# R3S601.net
KiCad netlist of a schematic drawn in Altium Designer
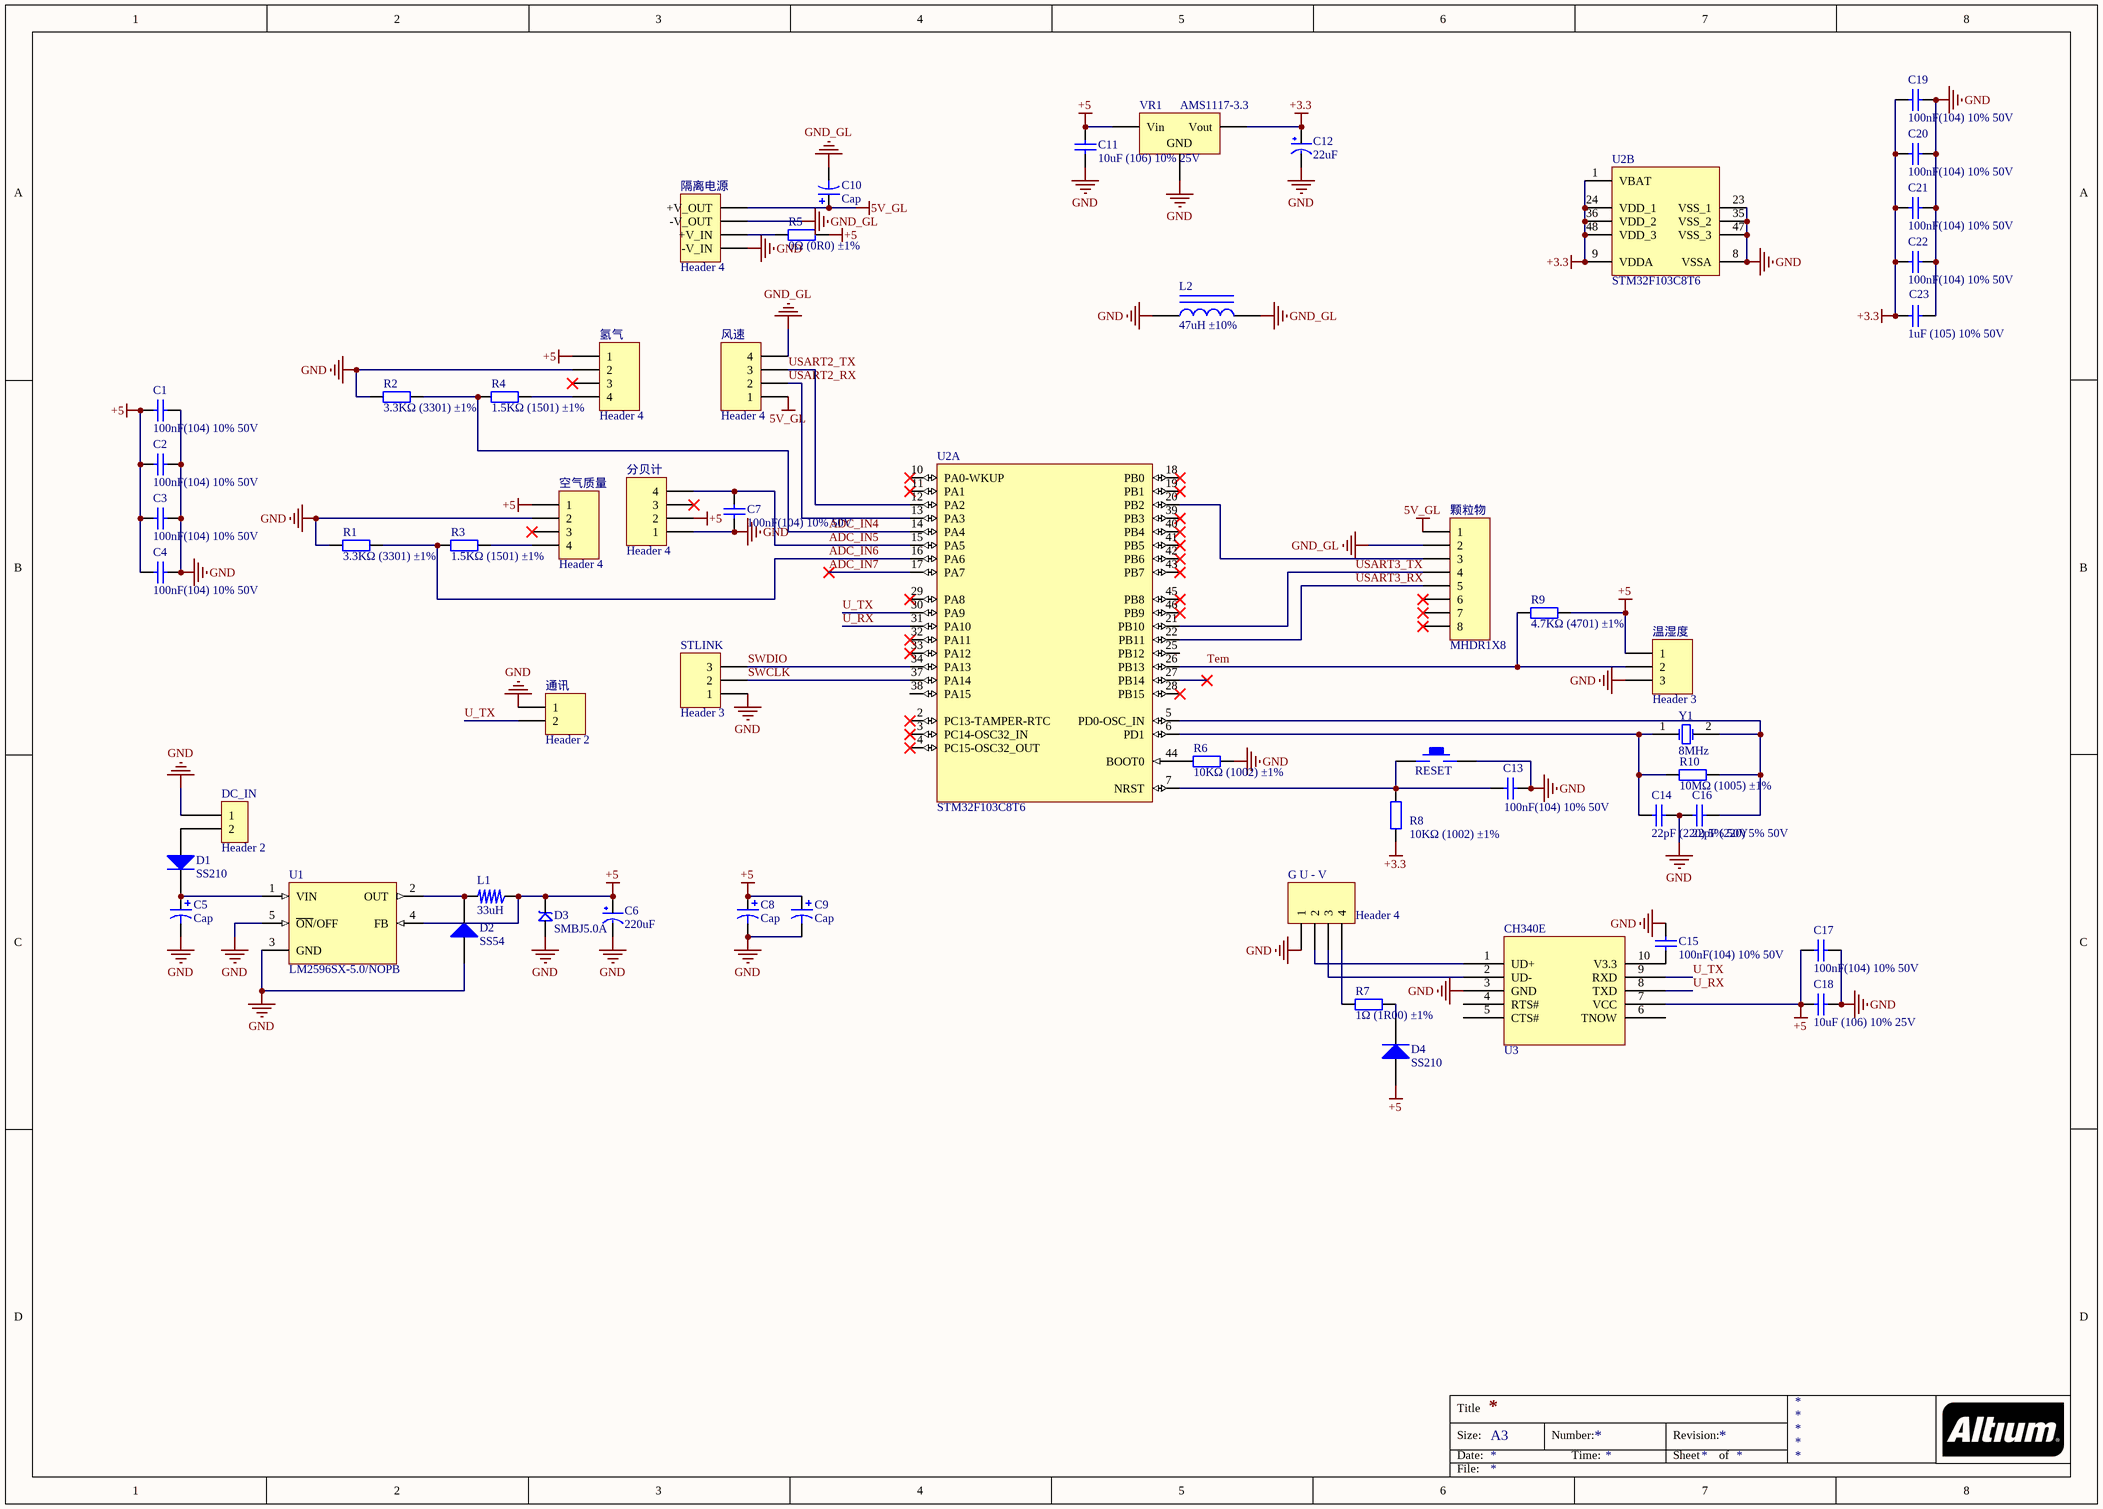
[diagram p0: R3S601.SchDoc]

(export (version "E")
  (design (tool "Eeschema 10.0.6"))
  (components
    (comp (ref "C1")
      (value "100nF(104) 10% 50V")
      (footprint "LC-0805_C")
      (description "贴片电容")
      (libsource (lib "Miscellaneous Devices LC") (part "0805 100nF(104) 10% 50V"))
    )
    (comp (ref "C2")
      (value "100nF(104) 10% 50V")
      (footprint "LC-0805_C")
      (description "贴片电容")
      (libsource (lib "Miscellaneous Devices LC") (part "0805 100nF(104) 10% 50V"))
    )
    (comp (ref "C3")
      (value "100nF(104) 10% 50V")
      (footprint "LC-0805_C")
      (description "贴片电容")
      (libsource (lib "Miscellaneous Devices LC") (part "0805 100nF(104) 10% 50V"))
    )
    (comp (ref "C4")
      (value "100nF(104) 10% 50V")
      (footprint "LC-0805_C")
      (description "贴片电容")
      (libsource (lib "Miscellaneous Devices LC") (part "0805 100nF(104) 10% 50V"))
    )
    (comp (ref "C5")
      (value "Cap")
      (footprint "CAP-DIP-3.5")
      (description "Cap_DIP")
      (libsource (lib "AD_Chip_Y") (part "Cap_DIP"))
    )
    (comp (ref "C6")
      (value "220uF")
      (footprint "CC6.56.5")
      (libsource (lib "Explorer STM32F407封装库") (part "CAP"))
    )
    (comp (ref "C7")
      (value "100nF(104) 10% 50V")
      (footprint "LC-0805_C")
      (description "贴片电容")
      (libsource (lib "Miscellaneous Devices LC") (part "0805 100nF(104) 10% 50V"))
    )
    (comp (ref "C8")
      (value "Cap")
      (footprint "CAP-DIP-3.5")
      (description "Cap_DIP")
      (libsource (lib "AD_Chip_Y") (part "Cap_DIP"))
    )
    (comp (ref "C9")
      (value "Cap")
      (footprint "CAP-DIP-5.0")
      (description "Cap_DIP")
      (libsource (lib "AD_Chip_Y") (part "Cap_DIP"))
    )
    (comp (ref "C10")
      (value "Cap")
      (footprint "CAP-DIP-3.5")
      (description "Cap_DIP")
      (libsource (lib "AD_Chip_Y") (part "Cap_DIP"))
    )
    (comp (ref "C11")
      (value "10uF (106) 10% 25V")
      (footprint "LC-0805_C")
      (description "贴片电容")
      (libsource (lib "Miscellaneous Devices LC") (part "0805 10uF (106) 10% 25V"))
    )
    (comp (ref "C12")
      (value "22uF")
      (footprint "CC6.56.5")
      (libsource (lib "Explorer STM32F407封装库") (part "CAP"))
    )
    (comp (ref "C13")
      (value "100nF(104) 10% 50V")
      (footprint "LC-0805_C")
      (description "贴片电容")
      (libsource (lib "Miscellaneous Devices LC") (part "0805 100nF(104) 10% 50V"))
    )
    (comp (ref "C14")
      (value "22pF (220) 5% 50V")
      (footprint "LC-0805_C")
      (description "贴片电容")
      (libsource (lib "Miscellaneous Devices LC") (part "0805 22pF (220) 5% 50V"))
    )
    (comp (ref "C15")
      (value "100nF(104) 10% 50V")
      (footprint "LC-0805_C")
      (description "贴片电容")
      (libsource (lib "Miscellaneous Devices LC") (part "0805 100nF(104) 10% 50V"))
    )
    (comp (ref "C16")
      (value "22pF (220) 5% 50V")
      (footprint "LC-0805_C")
      (description "贴片电容")
      (libsource (lib "Miscellaneous Devices LC") (part "0805 22pF (220) 5% 50V"))
    )
    (comp (ref "C17")
      (value "100nF(104) 10% 50V")
      (footprint "LC-0805_C")
      (description "贴片电容")
      (libsource (lib "Miscellaneous Devices LC") (part "0805 100nF(104) 10% 50V"))
    )
    (comp (ref "C18")
      (value "10uF (106) 10% 25V")
      (footprint "LC-0805_C")
      (description "贴片电容")
      (libsource (lib "Miscellaneous Devices LC") (part "0805 10uF (106) 10% 25V"))
    )
    (comp (ref "C19")
      (value "100nF(104) 10% 50V")
      (footprint "LC-0805_C")
      (description "贴片电容")
      (libsource (lib "Miscellaneous Devices LC") (part "0805 100nF(104) 10% 50V"))
    )
    (comp (ref "C20")
      (value "100nF(104) 10% 50V")
      (footprint "LC-0805_C")
      (description "贴片电容")
      (libsource (lib "Miscellaneous Devices LC") (part "0805 100nF(104) 10% 50V"))
    )
    (comp (ref "C21")
      (value "100nF(104) 10% 50V")
      (footprint "LC-0805_C")
      (description "贴片电容")
      (libsource (lib "Miscellaneous Devices LC") (part "0805 100nF(104) 10% 50V"))
    )
    (comp (ref "C22")
      (value "100nF(104) 10% 50V")
      (footprint "LC-0805_C")
      (description "贴片电容")
      (libsource (lib "Miscellaneous Devices LC") (part "0805 100nF(104) 10% 50V"))
    )
    (comp (ref "C23")
      (value "1uF (105) 10% 50V")
      (footprint "LC-0805_C")
      (description "贴片电容")
      (libsource (lib "Miscellaneous Devices LC") (part "0805 1uF (105) 10% 50V"))
    )
    (comp (ref "D1")
      (value "SS210")
      (footprint "LC-SMA(DO-214AC)_S1")
      (description "二极管")
      (libsource (lib "Miscellaneous Devices LC") (part "SMA(DO-214AC) SS210"))
    )
    (comp (ref "D2")
      (value "SS54")
      (footprint "LC-SMA(DO-214AC)_S1")
      (description "二极管")
      (libsource (lib "Miscellaneous Devices LC") (part "SMA(DO-214AC) SS54"))
    )
    (comp (ref "D3")
      (value "SMBJ5.0A")
      (footprint "SMBJ")
      (description "TVS")
      (libsource (lib "Explorer STM32F407封装库") (part "SMBJ"))
    )
    (comp (ref "D4")
      (value "SS210")
      (footprint "LC-SMA(DO-214AC)_S1")
      (description "二极管")
      (libsource (lib "Miscellaneous Devices LC") (part "SMA(DO-214AC) SS210"))
    )
    (comp (ref "DC_IN")
      (value "Header 2")
      (footprint "VH-2A - Circle Hole")
      (description "贴片2p座")
      (libsource (lib "AD_Chip_Y") (part "Header 2"))
    )
    (comp (ref "G U - V")
      (value "Header 4")
      (footprint "HDR1X4")
      (description "Header, 4-Pin")
      (fields (field (name "PUBLISHER") "Altium Limited"))
      (libsource (lib "Miscellaneous Connectors") (part "Header 4"))
    )
    (comp (ref "L1")
      (value "33uH")
      (footprint "L_SOP74")
      (libsource (lib "Explorer STM32F407封装库") (part "L_SOP"))
    )
    (comp (ref "L2")
      (value "47uH ±10%")
      (footprint "LC-0805_L")
      (description "贴片电感")
      (libsource (lib "Miscellaneous Devices LC") (part "0805 47uH 10%"))
    )
    (comp (ref "R1")
      (value "3.3KΩ (3301) ±1%")
      (footprint "LC-0805_R")
      (description "贴片电阻")
      (libsource (lib "Miscellaneous Devices LC") (part "0805 3.3KΩ (3301) 1%"))
    )
    (comp (ref "R2")
      (value "3.3KΩ (3301) ±1%")
      (footprint "LC-0805_R")
      (description "贴片电阻")
      (libsource (lib "Miscellaneous Devices LC") (part "0805 3.3KΩ (3301) 1%"))
    )
    (comp (ref "R3")
      (value "1.5KΩ (1501) ±1%")
      (footprint "LC-0805_R")
      (description "贴片电阻")
      (libsource (lib "Miscellaneous Devices LC") (part "0805 1.5KΩ (1501) 1%"))
    )
    (comp (ref "R4")
      (value "1.5KΩ (1501) ±1%")
      (footprint "LC-0805_R")
      (description "贴片电阻")
      (libsource (lib "Miscellaneous Devices LC") (part "0805 1.5KΩ (1501) 1%"))
    )
    (comp (ref "R5")
      (value "0Ω (0R0) ±1%")
      (footprint "LC-0603_R")
      (description "贴片电阻")
      (libsource (lib "Miscellaneous Devices LC") (part "0603 0Ω (0R0) 1%"))
    )
    (comp (ref "R6")
      (value "10KΩ (1002) ±1%")
      (footprint "LC-0805_R")
      (description "贴片电阻")
      (libsource (lib "") (part "0805 10KΩ (1002) 1%_1"))
    )
    (comp (ref "R7")
      (value "1Ω (1R00) ±1%")
      (footprint "LC-0603_R")
      (description "贴片电阻")
      (libsource (lib "Miscellaneous Devices LC") (part "0603 1Ω (1R00) 1%"))
    )
    (comp (ref "R8")
      (value "10KΩ (1002) ±1%")
      (footprint "LC-0805_R")
      (description "贴片电阻")
      (libsource (lib "Miscellaneous Devices LC") (part "0805 10KΩ (1002) 1%"))
    )
    (comp (ref "R9")
      (value "4.7KΩ (4701) ±1%")
      (footprint "LC-0805_R")
      (description "贴片电阻")
      (libsource (lib "Miscellaneous Devices LC") (part "0805 4.7KΩ (4701) 1%"))
    )
    (comp (ref "R10")
      (value "10MΩ (1005) ±1%")
      (footprint "LC-0805_R")
      (description "贴片电阻")
      (libsource (lib "Miscellaneous Devices LC") (part "0805 10MΩ (1005) 1%"))
    )
    (comp (ref "RESET")
      (value "KEY_M")
      (footprint "KEY_M")
      (libsource (lib "Explorer STM32F407封装库") (part "KEY_M"))
    )
    (comp (ref "STLINK")
      (value "Header 3")
      (footprint "HDR1X3")
      (description "Header, 3-Pin")
      (fields (field (name "PUBLISHER") "Altium Limited"))
      (libsource (lib "Miscellaneous Connectors") (part "Header 3"))
    )
    (comp (ref "U1")
      (value "LM2596SX-5.0/NOPB")
      (footprint "LC-TO-263-5")
      (description "DC-DC芯片")
      (libsource (lib "Miscellaneous Devices LC") (part "LM2596SX-5.0/NOPB"))
    )
    (comp (ref "U2")
      (value "STM32F103C8T6")
      (footprint "LC-LQFP-48_7x7x05P")
      (description "ARM")
      (libsource (lib "Miscellaneous Devices LC") (part "STM32F103C8T6"))
    )
    (comp (ref "U3")
      (value "CH340E")
      (footprint "LC-MSOP-10")
      (description "USB")
      (libsource (lib "AD_Chip_Y") (part "CH340E"))
    )
    (comp (ref "VR1")
      (value "AMS1117-3.3")
      (footprint "LC-SOT-223")
      (description "低压差线性稳压(LDO)")
      (libsource (lib "Miscellaneous Devices LC") (part "SOT-223 AMS1117-3.3"))
    )
    (comp (ref "Y1")
      (value "8MHz")
      (footprint "XTAL_US")
      (description "Crystal Oscillator")
      (fields (field (name "PUBLISHER") "Altium Limited"))
      (libsource (lib "Explorer STM32F407封装库") (part "XTAL"))
    )
    (comp (ref "分贝计")
      (value "Header 4")
      (footprint "HDR1X4")
      (description "Header, 4-Pin")
      (fields (field (name "PUBLISHER") "Altium Limited"))
      (libsource (lib "") (part "Header 4_1"))
    )
    (comp (ref "氢气")
      (value "Header 4")
      (footprint "HDR1X4")
      (description "Header, 4-Pin")
      (fields (field (name "PUBLISHER") "Altium Limited"))
      (libsource (lib "") (part "Header 4_2"))
    )
    (comp (ref "温湿度")
      (value "Header 3")
      (footprint "HDR1X3")
      (description "Header, 3-Pin")
      (fields (field (name "PUBLISHER") "Altium Limited"))
      (libsource (lib "") (part "Header 3_1"))
    )
    (comp (ref "空气质量")
      (value "Header 4")
      (footprint "HDR1X4")
      (description "Header, 4-Pin")
      (fields (field (name "PUBLISHER") "Altium Limited"))
      (libsource (lib "") (part "Header 4_2"))
    )
    (comp (ref "通讯")
      (value "Header 2")
      (footprint "HDR1X2")
      (description "Header, 2-Pin")
      (fields (field (name "PUBLISHER") "Altium Limited"))
      (libsource (lib "Miscellaneous Connectors") (part "Header 2"))
    )
    (comp (ref "隔离电源")
      (value "Header 4")
      (footprint "HDR1X4")
      (description "Header, 4-Pin")
      (fields (field (name "PUBLISHER") "Altium Limited"))
      (libsource (lib "") (part "Header 4_3"))
    )
    (comp (ref "颗粒物")
      (value "MHDR1X8")
      (footprint "MHDR1X8")
      (description "Header, 8-Pin")
      (fields (field (name "PUBLISHER") "Altium Limited"))
      (libsource (lib "Miscellaneous Connectors") (part "MHDR1X8"))
    )
    (comp (ref "风速")
      (value "Header 4")
      (footprint "HDR1X4")
      (description "Header, 4-Pin")
      (fields (field (name "PUBLISHER") "Altium Limited"))
      (libsource (lib "") (part "Header 4_1"))
    )
  )
  (nets
    (net (code "1") (name "+3.3") (class "Default")
      (node (ref "C12") (pin "1") (pinfunction "VCC_1") (pintype "passive"))
      (node (ref "C19") (pin "2") (pinfunction "2_2") (pintype "passive"))
      (node (ref "C20") (pin "2") (pinfunction "2_2") (pintype "passive"))
      (node (ref "C21") (pin "2") (pinfunction "2_2") (pintype "passive"))
      (node (ref "C22") (pin "2") (pinfunction "2_2") (pintype "passive"))
      (node (ref "C23") (pin "2") (pinfunction "2_2") (pintype "passive"))
      (node (ref "R8") (pin "1") (pinfunction "1_1") (pintype "passive"))
      (node (ref "U2") (pin "1") (pinfunction "VBAT_1") (pintype "power_in"))
      (node (ref "U2") (pin "24") (pinfunction "VDD_1_24") (pintype "power_in"))
      (node (ref "U2") (pin "36") (pinfunction "VDD_2_36") (pintype "power_in"))
      (node (ref "U2") (pin "48") (pinfunction "VDD_3_48") (pintype "power_in"))
      (node (ref "U2") (pin "9") (pinfunction "VDDA_9") (pintype "power_in"))
      (node (ref "VR1") (pin "2") (pinfunction "Vout_2") (pintype "passive"))
    )
    (net (code "2") (name "+5") (class "Default")
      (node (ref "C1") (pin "1") (pinfunction "1_1") (pintype "passive"))
      (node (ref "C11") (pin "2") (pinfunction "2_2") (pintype "passive"))
      (node (ref "C17") (pin "1") (pinfunction "1_1") (pintype "passive"))
      (node (ref "C18") (pin "1") (pinfunction "1_1") (pintype "passive"))
      (node (ref "C2") (pin "1") (pinfunction "1_1") (pintype "passive"))
      (node (ref "C3") (pin "1") (pinfunction "1_1") (pintype "passive"))
      (node (ref "C4") (pin "1") (pinfunction "1_1") (pintype "passive"))
      (node (ref "C6") (pin "1") (pinfunction "VCC_1") (pintype "passive"))
      (node (ref "C8") (pin "1") (pinfunction "1_1") (pintype "passive"))
      (node (ref "C9") (pin "1") (pinfunction "1_1") (pintype "passive"))
      (node (ref "D3") (pin "2") (pintype "passive"))
      (node (ref "D4") (pin "1") (pinfunction "A_1") (pintype "passive"))
      (node (ref "L1") (pin "1") (pinfunction "1_1") (pintype "passive"))
      (node (ref "R5") (pin "2") (pinfunction "2_2") (pintype "passive"))
      (node (ref "R9") (pin "2") (pinfunction "2_2") (pintype "passive"))
      (node (ref "U1") (pin "4") (pinfunction "FB_4") (pintype "input"))
      (node (ref "U3") (pin "7") (pinfunction "VCC_7") (pintype "passive"))
      (node (ref "VR1") (pin "3") (pinfunction "Vin_3") (pintype "passive"))
      (node (ref "分贝计") (pin "2") (pinfunction "2_2") (pintype "passive"))
      (node (ref "氢气") (pin "1") (pinfunction "1_1") (pintype "passive"))
      (node (ref "温湿度") (pin "1") (pinfunction "1_1") (pintype "passive"))
      (node (ref "空气质量") (pin "1") (pinfunction "1_1") (pintype "passive"))
    )
    (net (code "3") (name "/ADC_IN4") (class "Default")
      (node (ref "R2") (pin "2") (pinfunction "2_2") (pintype "passive"))
      (node (ref "R4") (pin "1") (pinfunction "1_1") (pintype "passive"))
      (node (ref "U2") (pin "14") (pinfunction "PA4_14") (pintype "bidirectional"))
    )
    (net (code "4") (name "/ADC_IN5") (class "Default")
      (node (ref "C7") (pin "2") (pinfunction "2_2") (pintype "passive"))
      (node (ref "U2") (pin "15") (pinfunction "PA5_15") (pintype "bidirectional"))
      (node (ref "分贝计") (pin "4") (pinfunction "4_4") (pintype "passive"))
    )
    (net (code "5") (name "/ADC_IN6") (class "Default")
      (node (ref "R1") (pin "2") (pinfunction "2_2") (pintype "passive"))
      (node (ref "R3") (pin "1") (pinfunction "1_1") (pintype "passive"))
      (node (ref "U2") (pin "16") (pinfunction "PA6_16") (pintype "bidirectional"))
    )
    (net (code "6") (name "/ADC_IN7") (class "Default")
      (node (ref "U2") (pin "17") (pinfunction "PA7_17") (pintype "bidirectional+no_connect"))
    )
    (net (code "7") (name "/SWCLK") (class "Default")
      (node (ref "STLINK") (pin "2") (pinfunction "2_2") (pintype "passive"))
      (node (ref "U2") (pin "37") (pinfunction "PA14_37") (pintype "bidirectional"))
    )
    (net (code "8") (name "/SWDIO") (class "Default")
      (node (ref "STLINK") (pin "3") (pinfunction "3_3") (pintype "passive"))
      (node (ref "U2") (pin "34") (pinfunction "PA13_34") (pintype "bidirectional"))
    )
    (net (code "9") (name "/Tem") (class "Default")
      (node (ref "R9") (pin "1") (pinfunction "1_1") (pintype "passive"))
      (node (ref "U2") (pin "26") (pinfunction "PB13_26") (pintype "bidirectional"))
      (node (ref "温湿度") (pin "2") (pinfunction "2_2") (pintype "passive"))
    )
    (net (code "10") (name "/USART2_RX") (class "Default")
      (node (ref "U2") (pin "13") (pinfunction "PA3_13") (pintype "bidirectional"))
      (node (ref "风速") (pin "2") (pinfunction "2_2") (pintype "passive"))
    )
    (net (code "11") (name "/USART2_TX") (class "Default")
      (node (ref "U2") (pin "12") (pinfunction "PA2_12") (pintype "bidirectional"))
      (node (ref "风速") (pin "3") (pinfunction "3_3") (pintype "passive"))
    )
    (net (code "12") (name "/USART3_RX") (class "Default")
      (node (ref "U2") (pin "22") (pinfunction "PB11_22") (pintype "bidirectional"))
      (node (ref "颗粒物") (pin "5") (pinfunction "5_5") (pintype "passive"))
    )
    (net (code "13") (name "/USART3_TX") (class "Default")
      (node (ref "U2") (pin "21") (pinfunction "PB10_21") (pintype "bidirectional"))
      (node (ref "颗粒物") (pin "4") (pinfunction "4_4") (pintype "passive"))
    )
    (net (code "14") (name "/U_RX") (class "Default")
      (node (ref "U2") (pin "31") (pinfunction "PA10_31") (pintype "bidirectional"))
      (node (ref "U3") (pin "8") (pinfunction "TXD_8") (pintype "passive"))
    )
    (net (code "15") (name "/U_TX") (class "Default")
      (node (ref "U2") (pin "30") (pinfunction "PA9_30") (pintype "bidirectional"))
      (node (ref "U3") (pin "9") (pinfunction "RXD_9") (pintype "passive"))
      (node (ref "通讯") (pin "2") (pinfunction "2_2") (pintype "passive"))
    )
    (net (code "16") (name "5V_GL") (class "Default")
      (node (ref "C10") (pin "1") (pinfunction "1_1") (pintype "passive"))
      (node (ref "隔离电源") (pin "4") (pinfunction "+V_OUT_4") (pintype "passive"))
      (node (ref "颗粒物") (pin "1") (pinfunction "1_1") (pintype "passive"))
      (node (ref "风速") (pin "1") (pinfunction "1_1") (pintype "passive"))
    )
    (net (code "17") (name "GND") (class "Default")
      (node (ref "C1") (pin "2") (pinfunction "2_2") (pintype "passive"))
      (node (ref "C11") (pin "1") (pinfunction "1_1") (pintype "passive"))
      (node (ref "C12") (pin "2") (pinfunction "GND_2") (pintype "passive"))
      (node (ref "C13") (pin "1") (pinfunction "1_1") (pintype "passive"))
      (node (ref "C14") (pin "2") (pinfunction "2_2") (pintype "passive"))
      (node (ref "C15") (pin "2") (pinfunction "2_2") (pintype "passive"))
      (node (ref "C16") (pin "1") (pinfunction "1_1") (pintype "passive"))
      (node (ref "C17") (pin "2") (pinfunction "2_2") (pintype "passive"))
      (node (ref "C18") (pin "2") (pinfunction "2_2") (pintype "passive"))
      (node (ref "C19") (pin "1") (pinfunction "1_1") (pintype "passive"))
      (node (ref "C2") (pin "2") (pinfunction "2_2") (pintype "passive"))
      (node (ref "C20") (pin "1") (pinfunction "1_1") (pintype "passive"))
      (node (ref "C21") (pin "1") (pinfunction "1_1") (pintype "passive"))
      (node (ref "C22") (pin "1") (pinfunction "1_1") (pintype "passive"))
      (node (ref "C23") (pin "1") (pinfunction "1_1") (pintype "passive"))
      (node (ref "C3") (pin "2") (pinfunction "2_2") (pintype "passive"))
      (node (ref "C4") (pin "2") (pinfunction "2_2") (pintype "passive"))
      (node (ref "C5") (pin "2") (pinfunction "2_2") (pintype "passive"))
      (node (ref "C6") (pin "2") (pinfunction "GND_2") (pintype "passive"))
      (node (ref "C7") (pin "1") (pinfunction "1_1") (pintype "passive"))
      (node (ref "C8") (pin "2") (pinfunction "2_2") (pintype "passive"))
      (node (ref "C9") (pin "2") (pinfunction "2_2") (pintype "passive"))
      (node (ref "D2") (pin "1") (pinfunction "A_1") (pintype "passive"))
      (node (ref "D3") (pin "1") (pintype "passive"))
      (node (ref "DC_IN") (pin "1") (pinfunction "1_1") (pintype "passive"))
      (node (ref "G U - V") (pin "1") (pinfunction "1_1") (pintype "passive"))
      (node (ref "L2") (pin "1") (pinfunction "1_1") (pintype "passive"))
      (node (ref "R1") (pin "1") (pinfunction "1_1") (pintype "passive"))
      (node (ref "R2") (pin "1") (pinfunction "1_1") (pintype "passive"))
      (node (ref "R6") (pin "2") (pinfunction "2_2") (pintype "passive"))
      (node (ref "RESET") (pin "2") (pinfunction "2_2") (pintype "passive"))
      (node (ref "STLINK") (pin "1") (pinfunction "1_1") (pintype "passive"))
      (node (ref "U1") (pin "3") (pinfunction "GND_3") (pintype "power_in"))
      (node (ref "U1") (pin "5") (pinfunction "~{ON}/OFF_5") (pintype "input"))
      (node (ref "U2") (pin "23") (pinfunction "VSS_1_23") (pintype "power_in"))
      (node (ref "U2") (pin "35") (pinfunction "VSS_2_35") (pintype "power_in"))
      (node (ref "U2") (pin "47") (pinfunction "VSS_3_47") (pintype "power_in"))
      (node (ref "U2") (pin "8") (pinfunction "VSSA_8") (pintype "power_in"))
      (node (ref "U3") (pin "3") (pinfunction "GND_3") (pintype "passive"))
      (node (ref "VR1") (pin "1") (pinfunction "GND_1") (pintype "passive"))
      (node (ref "分贝计") (pin "1") (pinfunction "1_1") (pintype "passive"))
      (node (ref "氢气") (pin "2") (pinfunction "2_2") (pintype "passive"))
      (node (ref "温湿度") (pin "3") (pinfunction "3_3") (pintype "passive"))
      (node (ref "空气质量") (pin "2") (pinfunction "2_2") (pintype "passive"))
      (node (ref "通讯") (pin "1") (pinfunction "1_1") (pintype "passive"))
      (node (ref "隔离电源") (pin "1") (pinfunction "-V_IN_1") (pintype "passive"))
    )
    (net (code "18") (name "GND_GL") (class "Default")
      (node (ref "C10") (pin "2") (pinfunction "2_2") (pintype "passive"))
      (node (ref "L2") (pin "2") (pinfunction "2_2") (pintype "passive"))
      (node (ref "隔离电源") (pin "3") (pinfunction "-V_OUT_3") (pintype "passive"))
      (node (ref "颗粒物") (pin "2") (pinfunction "2_2") (pintype "passive"))
      (node (ref "风速") (pin "4") (pinfunction "4_4") (pintype "passive"))
    )
    (net (code "19") (name "Net-(D1-A)") (class "Default")
      (node (ref "D1") (pin "1") (pinfunction "A_1") (pintype "passive"))
      (node (ref "DC_IN") (pin "2") (pinfunction "2_2") (pintype "passive"))
    )
    (net (code "20") (name "Net-(D1-K)") (class "Default")
      (node (ref "C5") (pin "1") (pinfunction "1_1") (pintype "passive"))
      (node (ref "D1") (pin "2") (pinfunction "K_2") (pintype "passive"))
      (node (ref "U1") (pin "1") (pinfunction "VIN_1") (pintype "input"))
    )
    (net (code "21") (name "Net-(D2-K)") (class "Default")
      (node (ref "D2") (pin "2") (pinfunction "K_2") (pintype "passive"))
      (node (ref "L1") (pin "2") (pinfunction "2_2") (pintype "passive"))
      (node (ref "U1") (pin "2") (pinfunction "OUT_2") (pintype "output"))
    )
    (net (code "22") (name "Net-(D4-K)") (class "Default")
      (node (ref "D4") (pin "2") (pinfunction "K_2") (pintype "passive"))
      (node (ref "R7") (pin "2") (pinfunction "2_2") (pintype "passive"))
    )
    (net (code "23") (name "Net-(G U - V-Pad4)") (class "Default")
      (node (ref "G U - V") (pin "4") (pinfunction "4_4") (pintype "passive"))
      (node (ref "R7") (pin "1") (pinfunction "1_1") (pintype "passive"))
    )
    (net (code "24") (name "Net-(R3-Pad2)") (class "Default")
      (node (ref "R3") (pin "2") (pinfunction "2_2") (pintype "passive"))
      (node (ref "空气质量") (pin "4") (pinfunction "4_4") (pintype "passive"))
    )
    (net (code "25") (name "Net-(R4-Pad2)") (class "Default")
      (node (ref "R4") (pin "2") (pinfunction "2_2") (pintype "passive"))
      (node (ref "氢气") (pin "4") (pinfunction "4_4") (pintype "passive"))
    )
    (net (code "26") (name "Net-(U2A-BOOT0)") (class "Default")
      (node (ref "R6") (pin "1") (pinfunction "1_1") (pintype "passive"))
      (node (ref "U2") (pin "44") (pinfunction "BOOT0_44") (pintype "input"))
    )
    (net (code "27") (name "Net-(U2A-NRST)") (class "Default")
      (node (ref "C13") (pin "2") (pinfunction "2_2") (pintype "passive"))
      (node (ref "R8") (pin "2") (pinfunction "2_2") (pintype "passive"))
      (node (ref "RESET") (pin "1") (pinfunction "1_1") (pintype "passive"))
      (node (ref "U2") (pin "7") (pinfunction "NRST_7") (pintype "bidirectional"))
    )
    (net (code "28") (name "Net-(U2A-PB2)") (class "Default")
      (node (ref "U2") (pin "20") (pinfunction "PB2_20") (pintype "bidirectional"))
      (node (ref "颗粒物") (pin "3") (pinfunction "3_3") (pintype "passive"))
    )
    (net (code "29") (name "Net-(U2A-PD0-OSC_IN)") (class "Default")
      (node (ref "C16") (pin "2") (pinfunction "2_2") (pintype "passive"))
      (node (ref "R10") (pin "2") (pinfunction "2_2") (pintype "passive"))
      (node (ref "U2") (pin "5") (pinfunction "PD0-OSC_IN_5") (pintype "bidirectional"))
      (node (ref "Y1") (pin "2") (pinfunction "OSC2_2") (pintype "passive"))
    )
    (net (code "30") (name "Net-(U2A-PD1)") (class "Default")
      (node (ref "C14") (pin "1") (pinfunction "1_1") (pintype "passive"))
      (node (ref "R10") (pin "1") (pinfunction "1_1") (pintype "passive"))
      (node (ref "U2") (pin "6") (pinfunction "PD1_6") (pintype "bidirectional"))
      (node (ref "Y1") (pin "1") (pinfunction "OSC1_1") (pintype "passive"))
    )
    (net (code "31") (name "Net-(U3-UD+)") (class "Default")
      (node (ref "G U - V") (pin "2") (pinfunction "2_2") (pintype "passive"))
      (node (ref "U3") (pin "1") (pinfunction "UD+_1") (pintype "passive"))
    )
    (net (code "32") (name "Net-(U3-UD-)") (class "Default")
      (node (ref "G U - V") (pin "3") (pinfunction "3_3") (pintype "passive"))
      (node (ref "U3") (pin "2") (pinfunction "UD-_2") (pintype "passive"))
    )
    (net (code "33") (name "Net-(U3-V3.3)") (class "Default")
      (node (ref "C15") (pin "1") (pinfunction "1_1") (pintype "passive"))
      (node (ref "U3") (pin "10") (pinfunction "V3.3_10") (pintype "passive"))
    )
    (net (code "34") (name "Net-(隔离电源-+V_IN)") (class "Default")
      (node (ref "R5") (pin "1") (pinfunction "1_1") (pintype "passive"))
      (node (ref "隔离电源") (pin "2") (pinfunction "+V_IN_2") (pintype "passive"))
    )
    (net (code "35") (name "unconnected-(U2A-PA0-WKUP-Pad10)") (class "Default")
      (node (ref "U2") (pin "10") (pinfunction "PA0-WKUP_10") (pintype "bidirectional+no_connect"))
    )
    (net (code "36") (name "unconnected-(U2A-PA1-Pad11)") (class "Default")
      (node (ref "U2") (pin "11") (pinfunction "PA1_11") (pintype "bidirectional+no_connect"))
    )
    (net (code "37") (name "unconnected-(U2A-PA8-Pad29)") (class "Default")
      (node (ref "U2") (pin "29") (pinfunction "PA8_29") (pintype "bidirectional+no_connect"))
    )
    (net (code "38") (name "unconnected-(U2A-PA11-Pad32)") (class "Default")
      (node (ref "U2") (pin "32") (pinfunction "PA11_32") (pintype "bidirectional+no_connect"))
    )
    (net (code "39") (name "unconnected-(U2A-PA12-Pad33)") (class "Default")
      (node (ref "U2") (pin "33") (pinfunction "PA12_33") (pintype "bidirectional+no_connect"))
    )
    (net (code "40") (name "unconnected-(U2A-PA15-Pad38)") (class "Default")
      (node (ref "U2") (pin "38") (pinfunction "PA15_38") (pintype "bidirectional"))
    )
    (net (code "41") (name "unconnected-(U2A-PB0-Pad18)") (class "Default")
      (node (ref "U2") (pin "18") (pinfunction "PB0_18") (pintype "bidirectional+no_connect"))
    )
    (net (code "42") (name "unconnected-(U2A-PB1-Pad19)") (class "Default")
      (node (ref "U2") (pin "19") (pinfunction "PB1_19") (pintype "bidirectional+no_connect"))
    )
    (net (code "43") (name "unconnected-(U2A-PB3-Pad39)") (class "Default")
      (node (ref "U2") (pin "39") (pinfunction "PB3_39") (pintype "bidirectional+no_connect"))
    )
    (net (code "44") (name "unconnected-(U2A-PB4-Pad40)") (class "Default")
      (node (ref "U2") (pin "40") (pinfunction "PB4_40") (pintype "bidirectional+no_connect"))
    )
    (net (code "45") (name "unconnected-(U2A-PB5-Pad41)") (class "Default")
      (node (ref "U2") (pin "41") (pinfunction "PB5_41") (pintype "bidirectional+no_connect"))
    )
    (net (code "46") (name "unconnected-(U2A-PB6-Pad42)") (class "Default")
      (node (ref "U2") (pin "42") (pinfunction "PB6_42") (pintype "bidirectional+no_connect"))
    )
    (net (code "47") (name "unconnected-(U2A-PB7-Pad43)") (class "Default")
      (node (ref "U2") (pin "43") (pinfunction "PB7_43") (pintype "bidirectional+no_connect"))
    )
    (net (code "48") (name "unconnected-(U2A-PB8-Pad45)") (class "Default")
      (node (ref "U2") (pin "45") (pinfunction "PB8_45") (pintype "bidirectional+no_connect"))
    )
    (net (code "49") (name "unconnected-(U2A-PB9-Pad46)") (class "Default")
      (node (ref "U2") (pin "46") (pinfunction "PB9_46") (pintype "bidirectional+no_connect"))
    )
    (net (code "50") (name "unconnected-(U2A-PB12-Pad25)") (class "Default")
      (node (ref "U2") (pin "25") (pinfunction "PB12_25") (pintype "bidirectional"))
    )
    (net (code "51") (name "unconnected-(U2A-PB14-Pad27)") (class "Default")
      (node (ref "U2") (pin "27") (pinfunction "PB14_27") (pintype "bidirectional+no_connect"))
    )
    (net (code "52") (name "unconnected-(U2A-PB15-Pad28)") (class "Default")
      (node (ref "U2") (pin "28") (pinfunction "PB15_28") (pintype "bidirectional+no_connect"))
    )
    (net (code "53") (name "unconnected-(U2A-PC13-TAMPER-RTC-Pad2)") (class "Default")
      (node (ref "U2") (pin "2") (pinfunction "PC13-TAMPER-RTC_2") (pintype "bidirectional+no_connect"))
    )
    (net (code "54") (name "unconnected-(U2A-PC14-OSC32_IN-Pad3)") (class "Default")
      (node (ref "U2") (pin "3") (pinfunction "PC14-OSC32_IN_3") (pintype "bidirectional+no_connect"))
    )
    (net (code "55") (name "unconnected-(U2A-PC15-OSC32_OUT-Pad4)") (class "Default")
      (node (ref "U2") (pin "4") (pinfunction "PC15-OSC32_OUT_4") (pintype "bidirectional+no_connect"))
    )
    (net (code "56") (name "unconnected-(U3-CTS#-Pad5)") (class "Default")
      (node (ref "U3") (pin "5") (pinfunction "CTS#_5") (pintype "passive"))
    )
    (net (code "57") (name "unconnected-(U3-RTS#-Pad4)") (class "Default")
      (node (ref "U3") (pin "4") (pinfunction "RTS#_4") (pintype "passive"))
    )
    (net (code "58") (name "unconnected-(U3-TNOW-Pad6)") (class "Default")
      (node (ref "U3") (pin "6") (pinfunction "TNOW_6") (pintype "passive"))
    )
    (net (code "59") (name "unconnected-(分贝计-Pad3)") (class "Default")
      (node (ref "分贝计") (pin "3") (pinfunction "3_3") (pintype "passive+no_connect"))
    )
    (net (code "60") (name "unconnected-(氢气-Pad3)") (class "Default")
      (node (ref "氢气") (pin "3") (pinfunction "3_3") (pintype "passive+no_connect"))
    )
    (net (code "61") (name "unconnected-(空气质量-Pad3)") (class "Default")
      (node (ref "空气质量") (pin "3") (pinfunction "3_3") (pintype "passive+no_connect"))
    )
    (net (code "62") (name "unconnected-(颗粒物-Pad6)") (class "Default")
      (node (ref "颗粒物") (pin "6") (pinfunction "6_6") (pintype "passive+no_connect"))
    )
    (net (code "63") (name "unconnected-(颗粒物-Pad7)") (class "Default")
      (node (ref "颗粒物") (pin "7") (pinfunction "7_7") (pintype "passive+no_connect"))
    )
    (net (code "64") (name "unconnected-(颗粒物-Pad8)") (class "Default")
      (node (ref "颗粒物") (pin "8") (pinfunction "8_8") (pintype "passive+no_connect"))
    )
  )
)
